# p02_power.net
KiCad netlist of a schematic drawn in Altium Designer
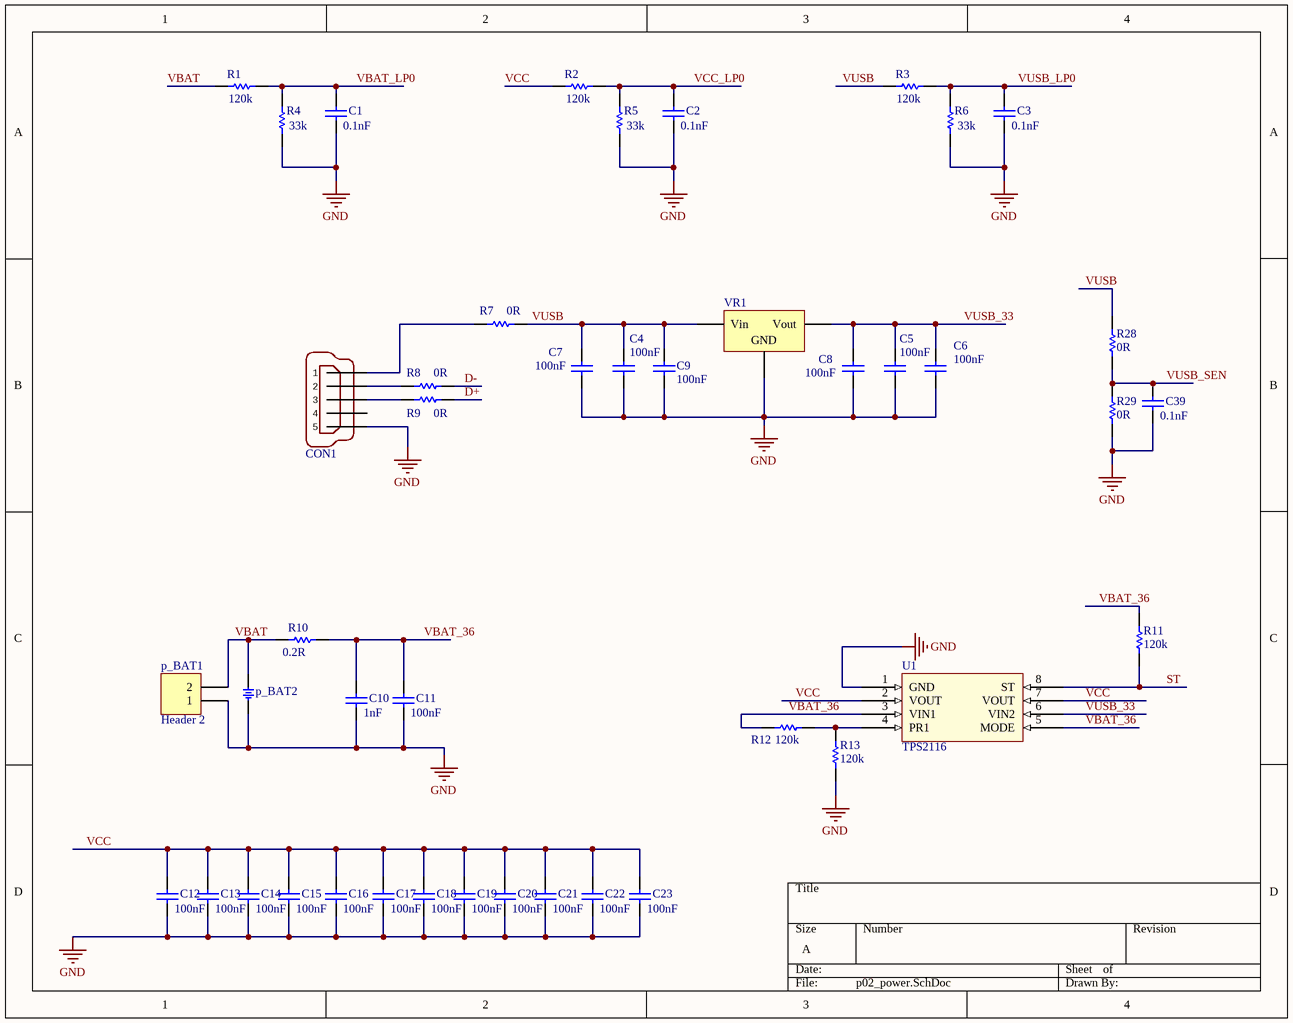
[diagram p0: p02_power.SchDoc]

(export (version "E")
  (design (tool "Eeschema 10.0.6"))
  (components
    (comp (ref "C1")
      (value "0.1nF")
      (footprint "Miscellaneous Devices:C0805")
      (description "Capacitor")
      (fields (field (name "Comment") "Cap") (field (name "PUBLISHER") "Altium Limited"))
      (libsource (lib "Miscellaneous Devices") (part "Cap"))
    )
    (comp (ref "C2")
      (value "0.1nF")
      (footprint "Miscellaneous Devices:C0805")
      (description "Capacitor")
      (fields (field (name "Comment") "Cap") (field (name "PUBLISHER") "Altium Limited"))
      (libsource (lib "Miscellaneous Devices") (part "Cap"))
    )
    (comp (ref "C3")
      (value "0.1nF")
      (footprint "Miscellaneous Devices:C0805")
      (description "Capacitor")
      (fields (field (name "Comment") "Cap") (field (name "PUBLISHER") "Altium Limited"))
      (libsource (lib "Miscellaneous Devices") (part "Cap"))
    )
    (comp (ref "C4")
      (value "100nF")
      (footprint "Miscellaneous Devices:C0805")
      (description "Capacitor")
      (fields (field (name "Comment") "Cap") (field (name "PUBLISHER") "Altium Limited"))
      (libsource (lib "Miscellaneous Devices") (part "Cap"))
    )
    (comp (ref "C5")
      (value "100nF")
      (footprint "Miscellaneous Devices:C0805")
      (description "Capacitor")
      (fields (field (name "Comment") "Cap") (field (name "PUBLISHER") "Altium Limited"))
      (libsource (lib "Miscellaneous Devices") (part "Cap"))
    )
    (comp (ref "C6")
      (value "100nF")
      (footprint "Miscellaneous Devices:C0805")
      (description "Capacitor")
      (fields (field (name "Comment") "Cap") (field (name "PUBLISHER") "Altium Limited"))
      (libsource (lib "Miscellaneous Devices") (part "Cap"))
    )
    (comp (ref "C7")
      (value "100nF")
      (footprint "Miscellaneous Devices:C0805")
      (description "Capacitor")
      (fields (field (name "Comment") "Cap") (field (name "PUBLISHER") "Altium Limited"))
      (libsource (lib "Miscellaneous Devices") (part "Cap"))
    )
    (comp (ref "C8")
      (value "100nF")
      (footprint "Miscellaneous Devices:C0805")
      (description "Capacitor")
      (fields (field (name "Comment") "Cap") (field (name "PUBLISHER") "Altium Limited"))
      (libsource (lib "Miscellaneous Devices") (part "Cap"))
    )
    (comp (ref "C9")
      (value "100nF")
      (footprint "Miscellaneous Devices:C0805")
      (description "Capacitor")
      (fields (field (name "Comment") "Cap") (field (name "PUBLISHER") "Altium Limited"))
      (libsource (lib "Miscellaneous Devices") (part "Cap"))
    )
    (comp (ref "C10")
      (value "1nF")
      (footprint "Miscellaneous Devices:C0805")
      (description "Capacitor")
      (fields (field (name "Comment") "Cap") (field (name "PUBLISHER") "Altium Limited"))
      (libsource (lib "Miscellaneous Devices") (part "Cap"))
    )
    (comp (ref "C11")
      (value "100nF")
      (footprint "Miscellaneous Devices:C0805")
      (description "Capacitor")
      (fields (field (name "Comment") "Cap") (field (name "PUBLISHER") "Altium Limited"))
      (libsource (lib "Miscellaneous Devices") (part "Cap"))
    )
    (comp (ref "C12")
      (value "100nF")
      (footprint "Miscellaneous Devices:C0805")
      (description "Capacitor")
      (fields (field (name "Comment") "Cap") (field (name "PUBLISHER") "Altium Limited"))
      (libsource (lib "Miscellaneous Devices") (part "Cap"))
    )
    (comp (ref "C13")
      (value "100nF")
      (footprint "Miscellaneous Devices:C0805")
      (description "Capacitor")
      (fields (field (name "Comment") "Cap") (field (name "PUBLISHER") "Altium Limited"))
      (libsource (lib "Miscellaneous Devices") (part "Cap"))
    )
    (comp (ref "C14")
      (value "100nF")
      (footprint "Miscellaneous Devices:C0805")
      (description "Capacitor")
      (fields (field (name "Comment") "Cap") (field (name "PUBLISHER") "Altium Limited"))
      (libsource (lib "Miscellaneous Devices") (part "Cap"))
    )
    (comp (ref "C15")
      (value "100nF")
      (footprint "Miscellaneous Devices:C0805")
      (description "Capacitor")
      (fields (field (name "Comment") "Cap") (field (name "PUBLISHER") "Altium Limited"))
      (libsource (lib "Miscellaneous Devices") (part "Cap"))
    )
    (comp (ref "C16")
      (value "100nF")
      (footprint "Miscellaneous Devices:C0805")
      (description "Capacitor")
      (fields (field (name "Comment") "Cap") (field (name "PUBLISHER") "Altium Limited"))
      (libsource (lib "Miscellaneous Devices") (part "Cap"))
    )
    (comp (ref "C17")
      (value "100nF")
      (footprint "Miscellaneous Devices:C0805")
      (description "Capacitor")
      (fields (field (name "Comment") "Cap") (field (name "PUBLISHER") "Altium Limited"))
      (libsource (lib "Miscellaneous Devices") (part "Cap"))
    )
    (comp (ref "C18")
      (value "100nF")
      (footprint "Miscellaneous Devices:C0805")
      (description "Capacitor")
      (fields (field (name "Comment") "Cap") (field (name "PUBLISHER") "Altium Limited"))
      (libsource (lib "Miscellaneous Devices") (part "Cap"))
    )
    (comp (ref "C19")
      (value "100nF")
      (footprint "Miscellaneous Devices:C0805")
      (description "Capacitor")
      (fields (field (name "Comment") "Cap") (field (name "PUBLISHER") "Altium Limited"))
      (libsource (lib "Miscellaneous Devices") (part "Cap"))
    )
    (comp (ref "C20")
      (value "100nF")
      (footprint "Miscellaneous Devices:C0805")
      (description "Capacitor")
      (fields (field (name "Comment") "Cap") (field (name "PUBLISHER") "Altium Limited"))
      (libsource (lib "Miscellaneous Devices") (part "Cap"))
    )
    (comp (ref "C21")
      (value "100nF")
      (footprint "Miscellaneous Devices:C0805")
      (description "Capacitor")
      (fields (field (name "Comment") "Cap") (field (name "PUBLISHER") "Altium Limited"))
      (libsource (lib "Miscellaneous Devices") (part "Cap"))
    )
    (comp (ref "C22")
      (value "100nF")
      (footprint "Miscellaneous Devices:C0805")
      (description "Capacitor")
      (fields (field (name "Comment") "Cap") (field (name "PUBLISHER") "Altium Limited"))
      (libsource (lib "Miscellaneous Devices") (part "Cap"))
    )
    (comp (ref "C23")
      (value "100nF")
      (footprint "Miscellaneous Devices:C0805")
      (description "Capacitor")
      (fields (field (name "Comment") "Cap") (field (name "PUBLISHER") "Altium Limited"))
      (libsource (lib "Miscellaneous Devices") (part "Cap"))
    )
    (comp (ref "C39")
      (value "0.1nF")
      (footprint "Miscellaneous Devices:C0805")
      (description "Capacitor")
      (fields (field (name "Comment") "Cap") (field (name "PUBLISHER") "Altium Limited"))
      (libsource (lib "Miscellaneous Devices") (part "Cap"))
    )
    (comp (ref "CON1")
      (value "897-43-005-00-100001")
      (footprint "USB-MINI-B-5P-SMD")
      (description "Connector,MiniUSB B port,5 position,Right Angle,Gold flash 30u,black,SMD")
      (fields (field (name "MANUFACTURER") "MILL-MAX"))
      (libsource (lib "LAUNCHXL-F28379D_REV2.0") (part "MINI-USB-32005-201"))
    )
    (comp (ref "p_BAT1")
      (value "Header 2")
      (footprint "HDR1X2")
      (description "Header, 2-Pin")
      (fields (field (name "PUBLISHER") "Altium Limited"))
      (libsource (lib "Miscellaneous Connectors") (part "Header 2"))
    )
    (comp (ref "p_BAT2")
      (value "~")
      (footprint "BTH2032")
      (description "BATTERY HOLDER, CR2032")
      (libsource (lib "BTH2032") (part "BATH_CR2032"))
    )
    (comp (ref "R1")
      (value "120k")
      (footprint "6-0805_M")
      (description "Resistor")
      (fields (field (name "Comment") "Res1") (field (name "PUBLISHER") "Altium Limited"))
      (libsource (lib "Miscellaneous Devices") (part "Res1"))
    )
    (comp (ref "R2")
      (value "120k")
      (footprint "6-0805_M")
      (description "Resistor")
      (fields (field (name "Comment") "Res1") (field (name "PUBLISHER") "Altium Limited"))
      (libsource (lib "Miscellaneous Devices") (part "Res1"))
    )
    (comp (ref "R3")
      (value "120k")
      (footprint "6-0805_M")
      (description "Resistor")
      (fields (field (name "Comment") "Res1") (field (name "PUBLISHER") "Altium Limited"))
      (libsource (lib "Miscellaneous Devices") (part "Res1"))
    )
    (comp (ref "R4")
      (value "33k")
      (footprint "6-0805_M")
      (description "Resistor")
      (fields (field (name "Comment") "Res1") (field (name "PUBLISHER") "Altium Limited"))
      (libsource (lib "Miscellaneous Devices") (part "Res1"))
    )
    (comp (ref "R5")
      (value "33k")
      (footprint "6-0805_M")
      (description "Resistor")
      (fields (field (name "Comment") "Res1") (field (name "PUBLISHER") "Altium Limited"))
      (libsource (lib "Miscellaneous Devices") (part "Res1"))
    )
    (comp (ref "R6")
      (value "33k")
      (footprint "6-0805_M")
      (description "Resistor")
      (fields (field (name "Comment") "Res1") (field (name "PUBLISHER") "Altium Limited"))
      (libsource (lib "Miscellaneous Devices") (part "Res1"))
    )
    (comp (ref "R7")
      (value "0R")
      (footprint "6-0805_M")
      (description "Resistor")
      (fields (field (name "PUBLISHER") "Altium Limited"))
      (libsource (lib "Miscellaneous Devices") (part "Res1"))
    )
    (comp (ref "R8")
      (value "0R")
      (footprint "6-0805_M")
      (description "Resistor")
      (fields (field (name "PUBLISHER") "Altium Limited"))
      (libsource (lib "Miscellaneous Devices") (part "Res1"))
    )
    (comp (ref "R9")
      (value "0R")
      (footprint "6-0805_M")
      (description "Resistor")
      (fields (field (name "PUBLISHER") "Altium Limited"))
      (libsource (lib "Miscellaneous Devices") (part "Res1"))
    )
    (comp (ref "R10")
      (value "0.2R")
      (footprint "6-0805_M")
      (description "Resistor")
      (fields (field (name "Comment") "Res1") (field (name "PUBLISHER") "Altium Limited"))
      (libsource (lib "Miscellaneous Devices") (part "Res1"))
    )
    (comp (ref "R11")
      (value "120k")
      (footprint "6-0805_M")
      (description "Resistor")
      (fields (field (name "Comment") "Res1") (field (name "PUBLISHER") "Altium Limited"))
      (libsource (lib "Miscellaneous Devices") (part "Res1"))
    )
    (comp (ref "R12")
      (value "120k")
      (footprint "6-0805_M")
      (description "Resistor")
      (fields (field (name "Comment") "Res1") (field (name "PUBLISHER") "Altium Limited"))
      (libsource (lib "Miscellaneous Devices") (part "Res1"))
    )
    (comp (ref "R13")
      (value "120k")
      (footprint "6-0805_M")
      (description "Resistor")
      (fields (field (name "Comment") "Res1") (field (name "PUBLISHER") "Altium Limited"))
      (libsource (lib "Miscellaneous Devices") (part "Res1"))
    )
    (comp (ref "R28")
      (value "0R")
      (footprint "6-0805_M")
      (description "Resistor")
      (fields (field (name "PUBLISHER") "Altium Limited"))
      (libsource (lib "Miscellaneous Devices") (part "Res1"))
    )
    (comp (ref "R29")
      (value "0R")
      (footprint "6-0805_M")
      (description "Resistor")
      (fields (field (name "PUBLISHER") "Altium Limited"))
      (libsource (lib "Miscellaneous Devices") (part "Res1"))
    )
    (comp (ref "U1")
      (value "TPS2116")
      (footprint "SOIC127P600X175-8N")
      (description "TPS2116 1.6 V to 5.5 V, 2.5-A Low IQ Power Mux with Manual and Priority Switchover")
      (libsource (lib "YamagotchiLib") (part "TPS2116"))
    )
    (comp (ref "VR1")
      (value "Volt Reg")
      (footprint "D2PAK_N")
      (description "Voltage Regulator")
      (fields (field (name "PUBLISHER") "Altium Limited"))
      (libsource (lib "Miscellaneous Devices") (part "Volt Reg"))
    )
  )
  (nets
    (net (code "1") (name "/D+") (class "Default")
      (node (ref "R9") (pin "1") (pinfunction "1_1") (pintype "passive"))
    )
    (net (code "2") (name "/D-") (class "Default")
      (node (ref "R8") (pin "1") (pinfunction "1_1") (pintype "passive"))
    )
    (net (code "3") (name "/ST") (class "Default")
      (node (ref "R11") (pin "2") (pinfunction "2_2") (pintype "passive"))
      (node (ref "U1") (pin "8") (pinfunction "ST_8") (pintype "input"))
    )
    (net (code "4") (name "/VBAT") (class "Default")
      (node (ref "R1") (pin "2") (pinfunction "2_2") (pintype "passive"))
      (node (ref "R10") (pin "2") (pinfunction "2_2") (pintype "passive"))
      (node (ref "p_BAT1") (pin "2") (pinfunction "2_2") (pintype "passive"))
      (node (ref "p_BAT2") (pin "1") (pinfunction "1_1") (pintype "passive"))
    )
    (net (code "5") (name "/VBAT_36") (class "Default")
      (node (ref "C10") (pin "2") (pinfunction "2_2") (pintype "passive"))
      (node (ref "C11") (pin "2") (pinfunction "2_2") (pintype "passive"))
      (node (ref "R10") (pin "1") (pinfunction "1_1") (pintype "passive"))
      (node (ref "R11") (pin "1") (pinfunction "1_1") (pintype "passive"))
      (node (ref "R12") (pin "1") (pinfunction "1_1") (pintype "passive"))
      (node (ref "U1") (pin "3") (pinfunction "VIN1_3") (pintype "input"))
      (node (ref "U1") (pin "5") (pinfunction "MODE_5") (pintype "input"))
    )
    (net (code "6") (name "/VBAT_LP0") (class "Default")
      (node (ref "C1") (pin "1") (pinfunction "1_1") (pintype "passive"))
      (node (ref "R1") (pin "1") (pinfunction "1_1") (pintype "passive"))
      (node (ref "R4") (pin "1") (pinfunction "1_1") (pintype "passive"))
    )
    (net (code "7") (name "/VCC") (class "Default")
      (node (ref "C12") (pin "2") (pinfunction "2_2") (pintype "passive"))
      (node (ref "C13") (pin "2") (pinfunction "2_2") (pintype "passive"))
      (node (ref "C14") (pin "2") (pinfunction "2_2") (pintype "passive"))
      (node (ref "C15") (pin "2") (pinfunction "2_2") (pintype "passive"))
      (node (ref "C16") (pin "2") (pinfunction "2_2") (pintype "passive"))
      (node (ref "C17") (pin "2") (pinfunction "2_2") (pintype "passive"))
      (node (ref "C18") (pin "2") (pinfunction "2_2") (pintype "passive"))
      (node (ref "C19") (pin "2") (pinfunction "2_2") (pintype "passive"))
      (node (ref "C20") (pin "2") (pinfunction "2_2") (pintype "passive"))
      (node (ref "C21") (pin "2") (pinfunction "2_2") (pintype "passive"))
      (node (ref "C22") (pin "2") (pinfunction "2_2") (pintype "passive"))
      (node (ref "C23") (pin "2") (pinfunction "2_2") (pintype "passive"))
      (node (ref "R2") (pin "2") (pinfunction "2_2") (pintype "passive"))
      (node (ref "U1") (pin "2") (pinfunction "VOUT_2") (pintype "input"))
      (node (ref "U1") (pin "7") (pinfunction "VOUT_7") (pintype "input"))
    )
    (net (code "8") (name "/VCC_LP0") (class "Default")
      (node (ref "C2") (pin "1") (pinfunction "1_1") (pintype "passive"))
      (node (ref "R2") (pin "1") (pinfunction "1_1") (pintype "passive"))
      (node (ref "R5") (pin "1") (pinfunction "1_1") (pintype "passive"))
    )
    (net (code "9") (name "/VUSB") (class "Default")
      (node (ref "C4") (pin "2") (pinfunction "2_2") (pintype "passive"))
      (node (ref "C7") (pin "2") (pinfunction "2_2") (pintype "passive"))
      (node (ref "C9") (pin "2") (pinfunction "2_2") (pintype "passive"))
      (node (ref "R28") (pin "1") (pinfunction "1_1") (pintype "passive"))
      (node (ref "R3") (pin "2") (pinfunction "2_2") (pintype "passive"))
      (node (ref "R7") (pin "1") (pinfunction "1_1") (pintype "passive"))
      (node (ref "VR1") (pin "1") (pinfunction "Vin_1") (pintype "passive"))
    )
    (net (code "10") (name "/VUSB_33") (class "Default")
      (node (ref "C5") (pin "2") (pinfunction "2_2") (pintype "passive"))
      (node (ref "C6") (pin "2") (pinfunction "2_2") (pintype "passive"))
      (node (ref "C8") (pin "2") (pinfunction "2_2") (pintype "passive"))
      (node (ref "U1") (pin "6") (pinfunction "VIN2_6") (pintype "input"))
      (node (ref "VR1") (pin "3") (pinfunction "Vout_3") (pintype "passive"))
    )
    (net (code "11") (name "/VUSB_LP0") (class "Default")
      (node (ref "C3") (pin "1") (pinfunction "1_1") (pintype "passive"))
      (node (ref "R3") (pin "1") (pinfunction "1_1") (pintype "passive"))
      (node (ref "R6") (pin "1") (pinfunction "1_1") (pintype "passive"))
    )
    (net (code "12") (name "/VUSB_SEN") (class "Default")
      (node (ref "C39") (pin "1") (pinfunction "1_1") (pintype "passive"))
      (node (ref "R28") (pin "2") (pinfunction "2_2") (pintype "passive"))
      (node (ref "R29") (pin "1") (pinfunction "1_1") (pintype "passive"))
    )
    (net (code "13") (name "GND") (class "Default")
      (node (ref "C1") (pin "2") (pinfunction "2_2") (pintype "passive"))
      (node (ref "C10") (pin "1") (pinfunction "1_1") (pintype "passive"))
      (node (ref "C11") (pin "1") (pinfunction "1_1") (pintype "passive"))
      (node (ref "C12") (pin "1") (pinfunction "1_1") (pintype "passive"))
      (node (ref "C13") (pin "1") (pinfunction "1_1") (pintype "passive"))
      (node (ref "C14") (pin "1") (pinfunction "1_1") (pintype "passive"))
      (node (ref "C15") (pin "1") (pinfunction "1_1") (pintype "passive"))
      (node (ref "C16") (pin "1") (pinfunction "1_1") (pintype "passive"))
      (node (ref "C17") (pin "1") (pinfunction "1_1") (pintype "passive"))
      (node (ref "C18") (pin "1") (pinfunction "1_1") (pintype "passive"))
      (node (ref "C19") (pin "1") (pinfunction "1_1") (pintype "passive"))
      (node (ref "C2") (pin "2") (pinfunction "2_2") (pintype "passive"))
      (node (ref "C20") (pin "1") (pinfunction "1_1") (pintype "passive"))
      (node (ref "C21") (pin "1") (pinfunction "1_1") (pintype "passive"))
      (node (ref "C22") (pin "1") (pinfunction "1_1") (pintype "passive"))
      (node (ref "C23") (pin "1") (pinfunction "1_1") (pintype "passive"))
      (node (ref "C3") (pin "2") (pinfunction "2_2") (pintype "passive"))
      (node (ref "C39") (pin "2") (pinfunction "2_2") (pintype "passive"))
      (node (ref "C4") (pin "1") (pinfunction "1_1") (pintype "passive"))
      (node (ref "C5") (pin "1") (pinfunction "1_1") (pintype "passive"))
      (node (ref "C6") (pin "1") (pinfunction "1_1") (pintype "passive"))
      (node (ref "C7") (pin "1") (pinfunction "1_1") (pintype "passive"))
      (node (ref "C8") (pin "1") (pinfunction "1_1") (pintype "passive"))
      (node (ref "C9") (pin "1") (pinfunction "1_1") (pintype "passive"))
      (node (ref "CON1") (pin "5") (pinfunction "5_5") (pintype "passive"))
      (node (ref "R13") (pin "2") (pinfunction "2_2") (pintype "passive"))
      (node (ref "R29") (pin "2") (pinfunction "2_2") (pintype "passive"))
      (node (ref "R4") (pin "2") (pinfunction "2_2") (pintype "passive"))
      (node (ref "R5") (pin "2") (pinfunction "2_2") (pintype "passive"))
      (node (ref "R6") (pin "2") (pinfunction "2_2") (pintype "passive"))
      (node (ref "U1") (pin "1") (pinfunction "GND_1") (pintype "input"))
      (node (ref "VR1") (pin "2") (pinfunction "GND_2") (pintype "passive"))
      (node (ref "p_BAT1") (pin "1") (pinfunction "1_1") (pintype "passive"))
      (node (ref "p_BAT2") (pin "2") (pinfunction "2_2") (pintype "passive"))
    )
    (net (code "14") (name "Net-(CON1-Pad1)") (class "Default")
      (node (ref "CON1") (pin "1") (pinfunction "1_1") (pintype "passive"))
      (node (ref "R7") (pin "2") (pinfunction "2_2") (pintype "passive"))
    )
    (net (code "15") (name "Net-(CON1-Pad2)") (class "Default")
      (node (ref "CON1") (pin "2") (pinfunction "2_2") (pintype "passive"))
      (node (ref "R8") (pin "2") (pinfunction "2_2") (pintype "passive"))
    )
    (net (code "16") (name "Net-(CON1-Pad3)") (class "Default")
      (node (ref "CON1") (pin "3") (pinfunction "3_3") (pintype "passive"))
      (node (ref "R9") (pin "2") (pinfunction "2_2") (pintype "passive"))
    )
    (net (code "17") (name "Net-(U1-PR1)") (class "Default")
      (node (ref "R12") (pin "2") (pinfunction "2_2") (pintype "passive"))
      (node (ref "R13") (pin "1") (pinfunction "1_1") (pintype "passive"))
      (node (ref "U1") (pin "4") (pinfunction "PR1_4") (pintype "input"))
    )
    (net (code "18") (name "unconnected-(CON1-Pad4)") (class "Default")
      (node (ref "CON1") (pin "4") (pinfunction "4_4") (pintype "passive"))
    )
  )
)
